# schematic.net
KiCad netlist of a schematic drawn in EAGLE
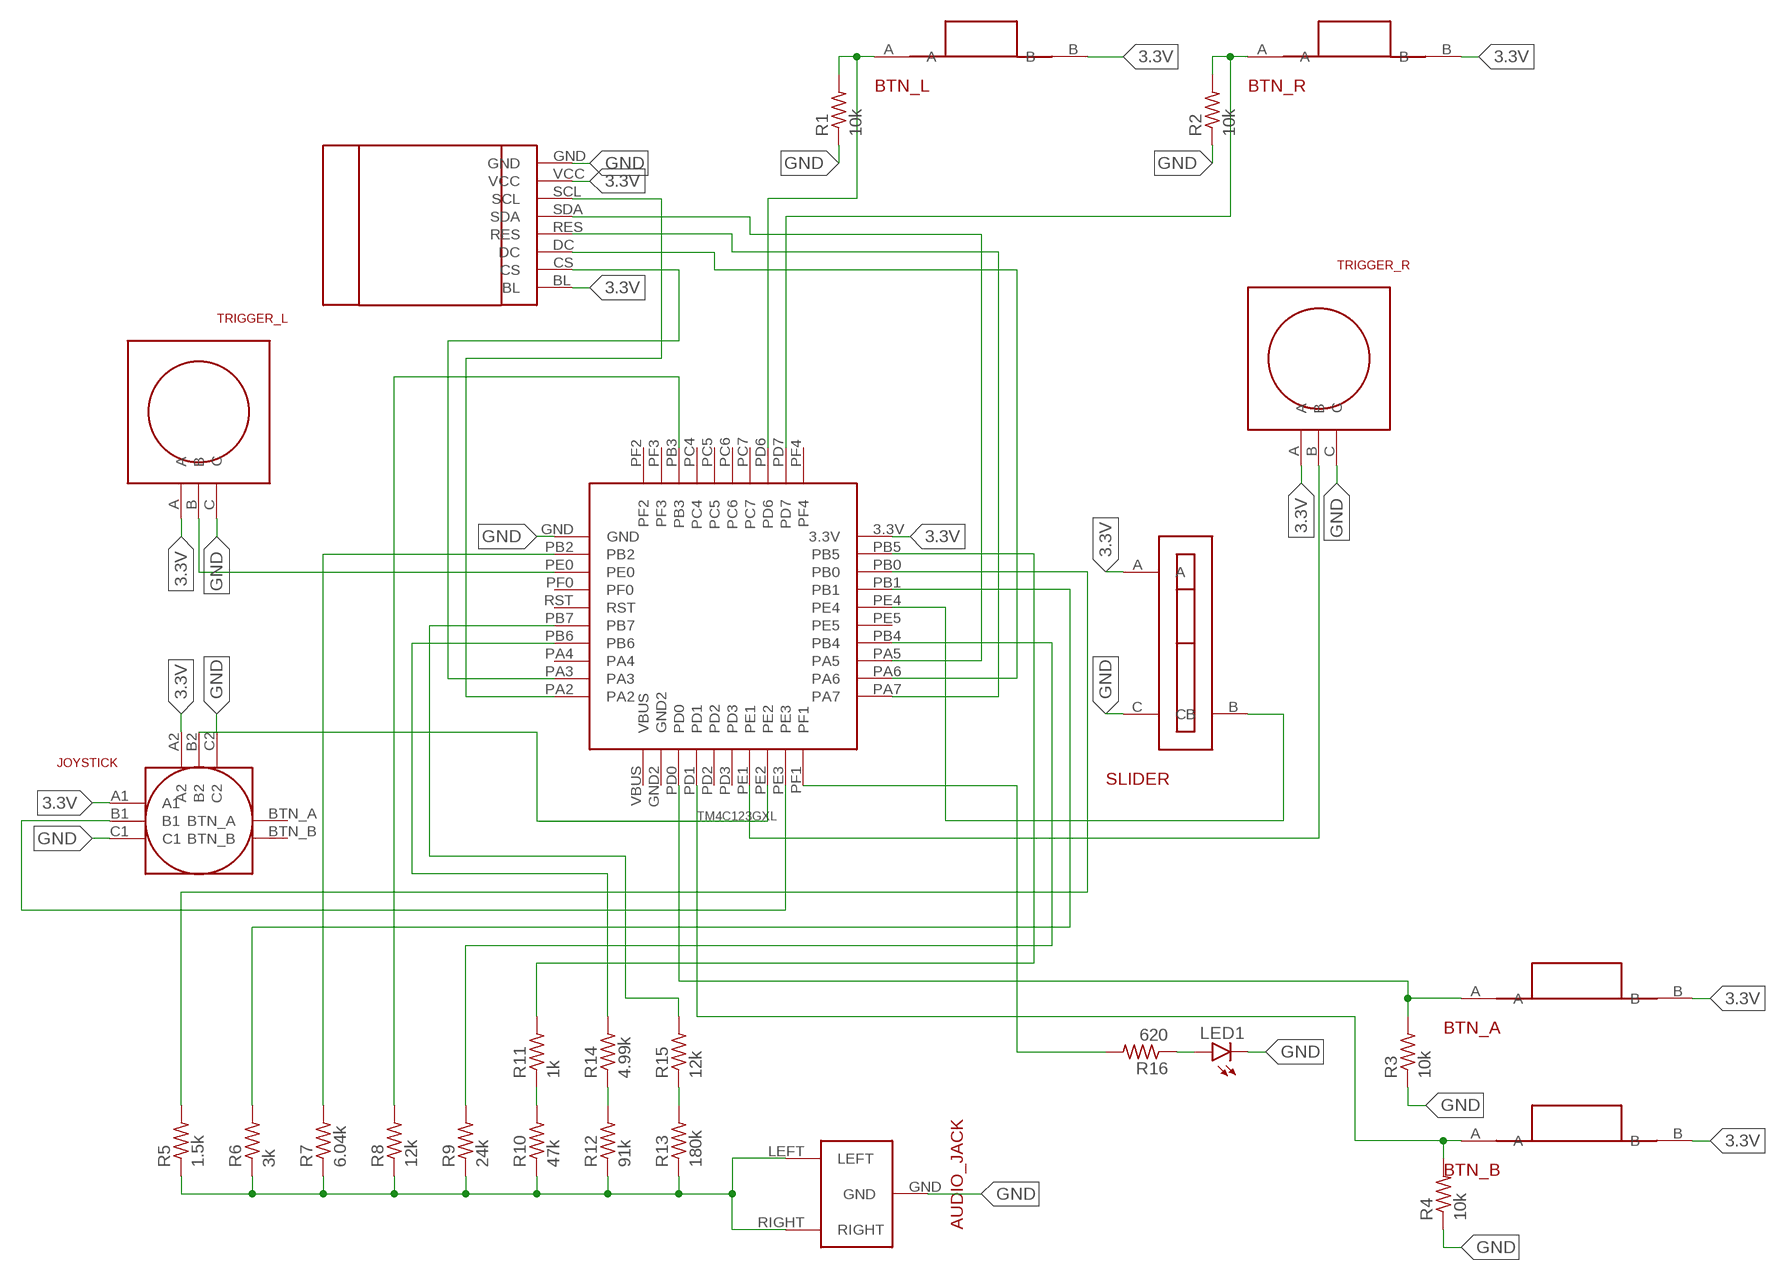
[diagram p0: schematic, sheet 1]

(export (version "E")
  (design (tool "Eeschema 10.0.6"))
  (components
    (comp (ref "LED1")
      (value "LEDCHIPLED_1206")
      (footprint "eagle-import:CHIPLED_1206")
      (libsource (lib "eagle-import") (part "LEDCHIPLED_1206"))
    )
    (comp (ref "R1")
      (value "10k")
      (footprint "eagle-import:R0805")
      (libsource (lib "eagle-import") (part "R-US_R0805"))
    )
    (comp (ref "R2")
      (value "10k")
      (footprint "eagle-import:R0805")
      (libsource (lib "eagle-import") (part "R-US_R0805"))
    )
    (comp (ref "R3")
      (value "10k")
      (footprint "eagle-import:R0805")
      (libsource (lib "eagle-import") (part "R-US_R0805"))
    )
    (comp (ref "R4")
      (value "10k")
      (footprint "eagle-import:R0805")
      (libsource (lib "eagle-import") (part "R-US_R0805"))
    )
    (comp (ref "R5")
      (value "1.5k")
      (footprint "eagle-import:R0805")
      (libsource (lib "eagle-import") (part "R-US_R0805"))
    )
    (comp (ref "R6")
      (value "3k")
      (footprint "eagle-import:R0805")
      (libsource (lib "eagle-import") (part "R-US_R0805"))
    )
    (comp (ref "R7")
      (value "6.04k")
      (footprint "eagle-import:R0805")
      (libsource (lib "eagle-import") (part "R-US_R0805"))
    )
    (comp (ref "R8")
      (value "12k")
      (footprint "eagle-import:R0805")
      (libsource (lib "eagle-import") (part "R-US_R0805"))
    )
    (comp (ref "R9")
      (value "24k")
      (footprint "eagle-import:R0805")
      (libsource (lib "eagle-import") (part "R-US_R0805"))
    )
    (comp (ref "R10")
      (value "47k")
      (footprint "eagle-import:R0805")
      (libsource (lib "eagle-import") (part "R-US_R0805"))
    )
    (comp (ref "R11")
      (value "1k")
      (footprint "eagle-import:R0805")
      (libsource (lib "eagle-import") (part "R-US_R0805"))
    )
    (comp (ref "R12")
      (value "91k")
      (footprint "eagle-import:R0805")
      (libsource (lib "eagle-import") (part "R-US_R0805"))
    )
    (comp (ref "R13")
      (value "180k")
      (footprint "eagle-import:R0805")
      (libsource (lib "eagle-import") (part "R-US_R0805"))
    )
    (comp (ref "R14")
      (value "4.99k")
      (footprint "eagle-import:R0805")
      (libsource (lib "eagle-import") (part "R-US_R0805"))
    )
    (comp (ref "R15")
      (value "12k")
      (footprint "eagle-import:R0805")
      (libsource (lib "eagle-import") (part "R-US_R0805"))
    )
    (comp (ref "R16")
      (value "620")
      (footprint "eagle-import:R0805")
      (libsource (lib "eagle-import") (part "R-US_R0805"))
    )
    (comp (ref "U$1")
      (value "TM4C123GXL")
      (footprint "eagle-import:TM4C123GXL")
      (libsource (lib "eagle-import") (part "TM4C123GXL"))
    )
    (comp (ref "U$2")
      (value "JOYSTICK")
      (footprint "eagle-import:JOYSTICK")
      (libsource (lib "eagle-import") (part "JOYSTICK"))
    )
    (comp (ref "U$3")
      (value "BTN_L")
      (footprint "eagle-import:RIGHT_ANGLE_BUTTON")
      (libsource (lib "eagle-import") (part "RIGHT_ANGLE_BUTTON"))
    )
    (comp (ref "U$4")
      (value "BTN_R")
      (footprint "eagle-import:RIGHT_ANGLE_BUTTON")
      (libsource (lib "eagle-import") (part "RIGHT_ANGLE_BUTTON"))
    )
    (comp (ref "U$5")
      (value "TRIGGER_L")
      (footprint "eagle-import:TRIGGER_L")
      (libsource (lib "eagle-import") (part "TRIGGER_L"))
    )
    (comp (ref "U$6")
      (value "TRIGGER_R")
      (footprint "eagle-import:TRIGGER_R")
      (libsource (lib "eagle-import") (part "TRIGGER_R"))
    )
    (comp (ref "U$7")
      (value "SLIDER")
      (footprint "eagle-import:SLIDER")
      (libsource (lib "eagle-import") (part "SLIDER"))
    )
    (comp (ref "U$8")
      (value "BTN_A")
      (footprint "eagle-import:BUTTON")
      (libsource (lib "eagle-import") (part "BUTTON"))
    )
    (comp (ref "U$9")
      (value "BTN_B")
      (footprint "eagle-import:BUTTON")
      (libsource (lib "eagle-import") (part "BUTTON"))
    )
    (comp (ref "U$10")
      (value "AUDIO_JACK")
      (footprint "eagle-import:AUDIO_JACK")
      (libsource (lib "eagle-import") (part "AUDIO_JACK"))
    )
    (comp (ref "U$11")
      (value "LCD_SCREEN")
      (footprint "eagle-import:LCD_SCREEN")
      (libsource (lib "eagle-import") (part "LCD_SCREEN"))
    )
  )
  (nets
    (net (code "1") (name "3.3V") (class "Default")
      (node (ref "U$1") (pin "3.3V") (pinfunction "3.3V_3.3V") (pintype "bidirectional"))
      (node (ref "U$11") (pin "BL") (pinfunction "BL_BL") (pintype "bidirectional"))
      (node (ref "U$11") (pin "VCC") (pinfunction "VCC_VCC") (pintype "bidirectional"))
      (node (ref "U$2") (pin "A1") (pinfunction "A1_A1") (pintype "bidirectional"))
      (node (ref "U$2") (pin "A2") (pinfunction "A2_A2") (pintype "bidirectional"))
      (node (ref "U$3") (pin "B") (pinfunction "B_B") (pintype "bidirectional"))
      (node (ref "U$4") (pin "B") (pinfunction "B_B") (pintype "bidirectional"))
      (node (ref "U$5") (pin "A") (pinfunction "A_A") (pintype "bidirectional"))
      (node (ref "U$6") (pin "A") (pinfunction "A_A") (pintype "bidirectional"))
      (node (ref "U$7") (pin "A") (pinfunction "A_A") (pintype "bidirectional"))
      (node (ref "U$8") (pin "B") (pinfunction "B_B") (pintype "bidirectional"))
      (node (ref "U$9") (pin "B") (pinfunction "B_B") (pintype "bidirectional"))
    )
    (net (code "2") (name "GND") (class "Default")
      (node (ref "LED1") (pin "C") (pinfunction "C_C") (pintype "passive"))
      (node (ref "R1") (pin "1") (pinfunction "1_1") (pintype "passive"))
      (node (ref "R2") (pin "1") (pinfunction "1_1") (pintype "passive"))
      (node (ref "R3") (pin "1") (pinfunction "1_1") (pintype "passive"))
      (node (ref "R4") (pin "1") (pinfunction "1_1") (pintype "passive"))
      (node (ref "U$1") (pin "GND") (pinfunction "GND_GND") (pintype "bidirectional"))
      (node (ref "U$10") (pin "GND") (pinfunction "GND_GND") (pintype "bidirectional"))
      (node (ref "U$11") (pin "GND") (pinfunction "GND_GND") (pintype "bidirectional"))
      (node (ref "U$2") (pin "C1") (pinfunction "C1_C1") (pintype "bidirectional"))
      (node (ref "U$2") (pin "C2") (pinfunction "C2_C2") (pintype "bidirectional"))
      (node (ref "U$5") (pin "C") (pinfunction "C_C") (pintype "bidirectional"))
      (node (ref "U$6") (pin "C") (pinfunction "C_C") (pintype "bidirectional"))
      (node (ref "U$7") (pin "C") (pinfunction "C_C") (pintype "bidirectional"))
    )
    (net (code "3") (name "Net-(LED1-PadA)") (class "Default")
      (node (ref "LED1") (pin "A") (pinfunction "A_A") (pintype "passive"))
      (node (ref "R16") (pin "1") (pinfunction "1_1") (pintype "passive"))
    )
    (net (code "4") (name "Net-(R1-Pad2)") (class "Default")
      (node (ref "R1") (pin "2") (pinfunction "2_2") (pintype "passive"))
      (node (ref "U$1") (pin "PD6") (pinfunction "PD6_PD6") (pintype "bidirectional"))
      (node (ref "U$3") (pin "A") (pinfunction "A_A") (pintype "bidirectional"))
    )
    (net (code "5") (name "Net-(R2-Pad2)") (class "Default")
      (node (ref "R2") (pin "2") (pinfunction "2_2") (pintype "passive"))
      (node (ref "U$1") (pin "PD7") (pinfunction "PD7_PD7") (pintype "bidirectional"))
      (node (ref "U$4") (pin "A") (pinfunction "A_A") (pintype "bidirectional"))
    )
    (net (code "6") (name "Net-(R3-Pad2)") (class "Default")
      (node (ref "R3") (pin "2") (pinfunction "2_2") (pintype "passive"))
      (node (ref "U$1") (pin "PD0") (pinfunction "PD0_PD0") (pintype "bidirectional"))
      (node (ref "U$8") (pin "A") (pinfunction "A_A") (pintype "bidirectional"))
    )
    (net (code "7") (name "Net-(R4-Pad2)") (class "Default")
      (node (ref "R4") (pin "2") (pinfunction "2_2") (pintype "passive"))
      (node (ref "U$1") (pin "PD1") (pinfunction "PD1_PD1") (pintype "bidirectional"))
      (node (ref "U$9") (pin "A") (pinfunction "A_A") (pintype "bidirectional"))
    )
    (net (code "8") (name "Net-(R5-Pad2)") (class "Default")
      (node (ref "R5") (pin "2") (pinfunction "2_2") (pintype "passive"))
      (node (ref "U$1") (pin "PB0") (pinfunction "PB0_PB0") (pintype "bidirectional"))
    )
    (net (code "9") (name "Net-(R6-Pad2)") (class "Default")
      (node (ref "R6") (pin "2") (pinfunction "2_2") (pintype "passive"))
      (node (ref "U$1") (pin "PB1") (pinfunction "PB1_PB1") (pintype "bidirectional"))
    )
    (net (code "10") (name "Net-(R7-Pad2)") (class "Default")
      (node (ref "R7") (pin "2") (pinfunction "2_2") (pintype "passive"))
      (node (ref "U$1") (pin "PB2") (pinfunction "PB2_PB2") (pintype "bidirectional"))
    )
    (net (code "11") (name "Net-(R8-Pad2)") (class "Default")
      (node (ref "R8") (pin "2") (pinfunction "2_2") (pintype "passive"))
      (node (ref "U$1") (pin "PB3") (pinfunction "PB3_PB3") (pintype "bidirectional"))
    )
    (net (code "12") (name "Net-(R9-Pad2)") (class "Default")
      (node (ref "R9") (pin "2") (pinfunction "2_2") (pintype "passive"))
      (node (ref "U$1") (pin "PB4") (pinfunction "PB4_PB4") (pintype "bidirectional"))
    )
    (net (code "13") (name "Net-(R10-Pad1)") (class "Default")
      (node (ref "R10") (pin "1") (pinfunction "1_1") (pintype "passive"))
      (node (ref "R12") (pin "1") (pinfunction "1_1") (pintype "passive"))
      (node (ref "R13") (pin "1") (pinfunction "1_1") (pintype "passive"))
      (node (ref "R5") (pin "1") (pinfunction "1_1") (pintype "passive"))
      (node (ref "R6") (pin "1") (pinfunction "1_1") (pintype "passive"))
      (node (ref "R7") (pin "1") (pinfunction "1_1") (pintype "passive"))
      (node (ref "R8") (pin "1") (pinfunction "1_1") (pintype "passive"))
      (node (ref "R9") (pin "1") (pinfunction "1_1") (pintype "passive"))
      (node (ref "U$10") (pin "LEFT") (pinfunction "LEFT_LEFT") (pintype "bidirectional"))
      (node (ref "U$10") (pin "RIGHT") (pinfunction "RIGHT_RIGHT") (pintype "bidirectional"))
    )
    (net (code "14") (name "Net-(R10-Pad2)") (class "Default")
      (node (ref "R10") (pin "2") (pinfunction "2_2") (pintype "passive"))
      (node (ref "R11") (pin "1") (pinfunction "1_1") (pintype "passive"))
    )
    (net (code "15") (name "Net-(R11-Pad2)") (class "Default")
      (node (ref "R11") (pin "2") (pinfunction "2_2") (pintype "passive"))
      (node (ref "U$1") (pin "PB5") (pinfunction "PB5_PB5") (pintype "bidirectional"))
    )
    (net (code "16") (name "Net-(R12-Pad2)") (class "Default")
      (node (ref "R12") (pin "2") (pinfunction "2_2") (pintype "passive"))
      (node (ref "R14") (pin "1") (pinfunction "1_1") (pintype "passive"))
    )
    (net (code "17") (name "Net-(R13-Pad2)") (class "Default")
      (node (ref "R13") (pin "2") (pinfunction "2_2") (pintype "passive"))
      (node (ref "R15") (pin "1") (pinfunction "1_1") (pintype "passive"))
    )
    (net (code "18") (name "Net-(R14-Pad2)") (class "Default")
      (node (ref "R14") (pin "2") (pinfunction "2_2") (pintype "passive"))
      (node (ref "U$1") (pin "PB6") (pinfunction "PB6_PB6") (pintype "bidirectional"))
    )
    (net (code "19") (name "Net-(R15-Pad2)") (class "Default")
      (node (ref "R15") (pin "2") (pinfunction "2_2") (pintype "passive"))
      (node (ref "U$1") (pin "PB7") (pinfunction "PB7_PB7") (pintype "bidirectional"))
    )
    (net (code "20") (name "Net-(R16-Pad2)") (class "Default")
      (node (ref "R16") (pin "2") (pinfunction "2_2") (pintype "passive"))
      (node (ref "U$1") (pin "PF1") (pinfunction "PF1_PF1") (pintype "bidirectional"))
    )
    (net (code "21") (name "Net-(U$1-PadPA2)") (class "Default")
      (node (ref "U$1") (pin "PA2") (pinfunction "PA2_PA2") (pintype "bidirectional"))
      (node (ref "U$11") (pin "SCL") (pinfunction "SCL_SCL") (pintype "bidirectional"))
    )
    (net (code "22") (name "Net-(U$1-PadPA3)") (class "Default")
      (node (ref "U$1") (pin "PA3") (pinfunction "PA3_PA3") (pintype "bidirectional"))
      (node (ref "U$11") (pin "CS") (pinfunction "CS_CS") (pintype "bidirectional"))
    )
    (net (code "23") (name "Net-(U$1-PadPA5)") (class "Default")
      (node (ref "U$1") (pin "PA5") (pinfunction "PA5_PA5") (pintype "bidirectional"))
      (node (ref "U$11") (pin "SDA") (pinfunction "SDA_SDA") (pintype "bidirectional"))
    )
    (net (code "24") (name "Net-(U$1-PadPA6)") (class "Default")
      (node (ref "U$1") (pin "PA6") (pinfunction "PA6_PA6") (pintype "bidirectional"))
      (node (ref "U$11") (pin "DC") (pinfunction "DC_DC") (pintype "bidirectional"))
    )
    (net (code "25") (name "Net-(U$1-PadPA7)") (class "Default")
      (node (ref "U$1") (pin "PA7") (pinfunction "PA7_PA7") (pintype "bidirectional"))
      (node (ref "U$11") (pin "RES") (pinfunction "RES_RES") (pintype "bidirectional"))
    )
    (net (code "26") (name "Net-(U$1-PadPE0)") (class "Default")
      (node (ref "U$1") (pin "PE0") (pinfunction "PE0_PE0") (pintype "bidirectional"))
      (node (ref "U$5") (pin "B") (pinfunction "B_B") (pintype "bidirectional"))
    )
    (net (code "27") (name "Net-(U$1-PadPE1)") (class "Default")
      (node (ref "U$1") (pin "PE1") (pinfunction "PE1_PE1") (pintype "bidirectional"))
      (node (ref "U$6") (pin "B") (pinfunction "B_B") (pintype "bidirectional"))
    )
    (net (code "28") (name "Net-(U$1-PadPE2)") (class "Default")
      (node (ref "U$1") (pin "PE2") (pinfunction "PE2_PE2") (pintype "bidirectional"))
      (node (ref "U$2") (pin "B2") (pinfunction "B2_B2") (pintype "bidirectional"))
    )
    (net (code "29") (name "Net-(U$1-PadPE3)") (class "Default")
      (node (ref "U$1") (pin "PE3") (pinfunction "PE3_PE3") (pintype "bidirectional"))
      (node (ref "U$2") (pin "B1") (pinfunction "B1_B1") (pintype "bidirectional"))
    )
    (net (code "30") (name "Net-(U$1-PadPE4)") (class "Default")
      (node (ref "U$1") (pin "PE4") (pinfunction "PE4_PE4") (pintype "bidirectional"))
      (node (ref "U$7") (pin "B") (pinfunction "B_B") (pintype "bidirectional"))
    )
    (net (code "31") (name "unconnected-(U$1-PadGND2)") (class "Default")
      (node (ref "U$1") (pin "GND2") (pinfunction "GND2_GND2") (pintype "bidirectional"))
    )
    (net (code "32") (name "unconnected-(U$1-PadPA4)") (class "Default")
      (node (ref "U$1") (pin "PA4") (pinfunction "PA4_PA4") (pintype "bidirectional"))
    )
    (net (code "33") (name "unconnected-(U$1-PadPC4)") (class "Default")
      (node (ref "U$1") (pin "PC4") (pinfunction "PC4_PC4") (pintype "bidirectional"))
    )
    (net (code "34") (name "unconnected-(U$1-PadPC5)") (class "Default")
      (node (ref "U$1") (pin "PC5") (pinfunction "PC5_PC5") (pintype "bidirectional"))
    )
    (net (code "35") (name "unconnected-(U$1-PadPC6)") (class "Default")
      (node (ref "U$1") (pin "PC6") (pinfunction "PC6_PC6") (pintype "bidirectional"))
    )
    (net (code "36") (name "unconnected-(U$1-PadPC7)") (class "Default")
      (node (ref "U$1") (pin "PC7") (pinfunction "PC7_PC7") (pintype "bidirectional"))
    )
    (net (code "37") (name "unconnected-(U$1-PadPD2)") (class "Default")
      (node (ref "U$1") (pin "PD2") (pinfunction "PD2_PD2") (pintype "bidirectional"))
    )
    (net (code "38") (name "unconnected-(U$1-PadPD3)") (class "Default")
      (node (ref "U$1") (pin "PD3") (pinfunction "PD3_PD3") (pintype "bidirectional"))
    )
    (net (code "39") (name "unconnected-(U$1-PadPE5)") (class "Default")
      (node (ref "U$1") (pin "PE5") (pinfunction "PE5_PE5") (pintype "bidirectional"))
    )
    (net (code "40") (name "unconnected-(U$1-PadPF0)") (class "Default")
      (node (ref "U$1") (pin "PF0") (pinfunction "PF0_PF0") (pintype "bidirectional"))
    )
    (net (code "41") (name "unconnected-(U$1-PadPF2)") (class "Default")
      (node (ref "U$1") (pin "PF2") (pinfunction "PF2_PF2") (pintype "bidirectional"))
    )
    (net (code "42") (name "unconnected-(U$1-PadPF3)") (class "Default")
      (node (ref "U$1") (pin "PF3") (pinfunction "PF3_PF3") (pintype "bidirectional"))
    )
    (net (code "43") (name "unconnected-(U$1-PadPF4)") (class "Default")
      (node (ref "U$1") (pin "PF4") (pinfunction "PF4_PF4") (pintype "bidirectional"))
    )
    (net (code "44") (name "unconnected-(U$1-PadRST)") (class "Default")
      (node (ref "U$1") (pin "RST") (pinfunction "RST_RST") (pintype "bidirectional"))
    )
    (net (code "45") (name "unconnected-(U$1-PadVBUS)") (class "Default")
      (node (ref "U$1") (pin "VBUS") (pinfunction "VBUS_VBUS") (pintype "bidirectional"))
    )
    (net (code "46") (name "unconnected-(U$2-PadBTN_A)") (class "Default")
      (node (ref "U$2") (pin "BTN_A") (pinfunction "BTN_A_BTN_A") (pintype "bidirectional"))
    )
    (net (code "47") (name "unconnected-(U$2-PadBTN_B)") (class "Default")
      (node (ref "U$2") (pin "BTN_B") (pinfunction "BTN_B_BTN_B") (pintype "bidirectional"))
    )
  )
)
